# 34-SERDES_AND_DISPLAY_INTERFACE.net
KiCad netlist of a schematic drawn in Altium Designer
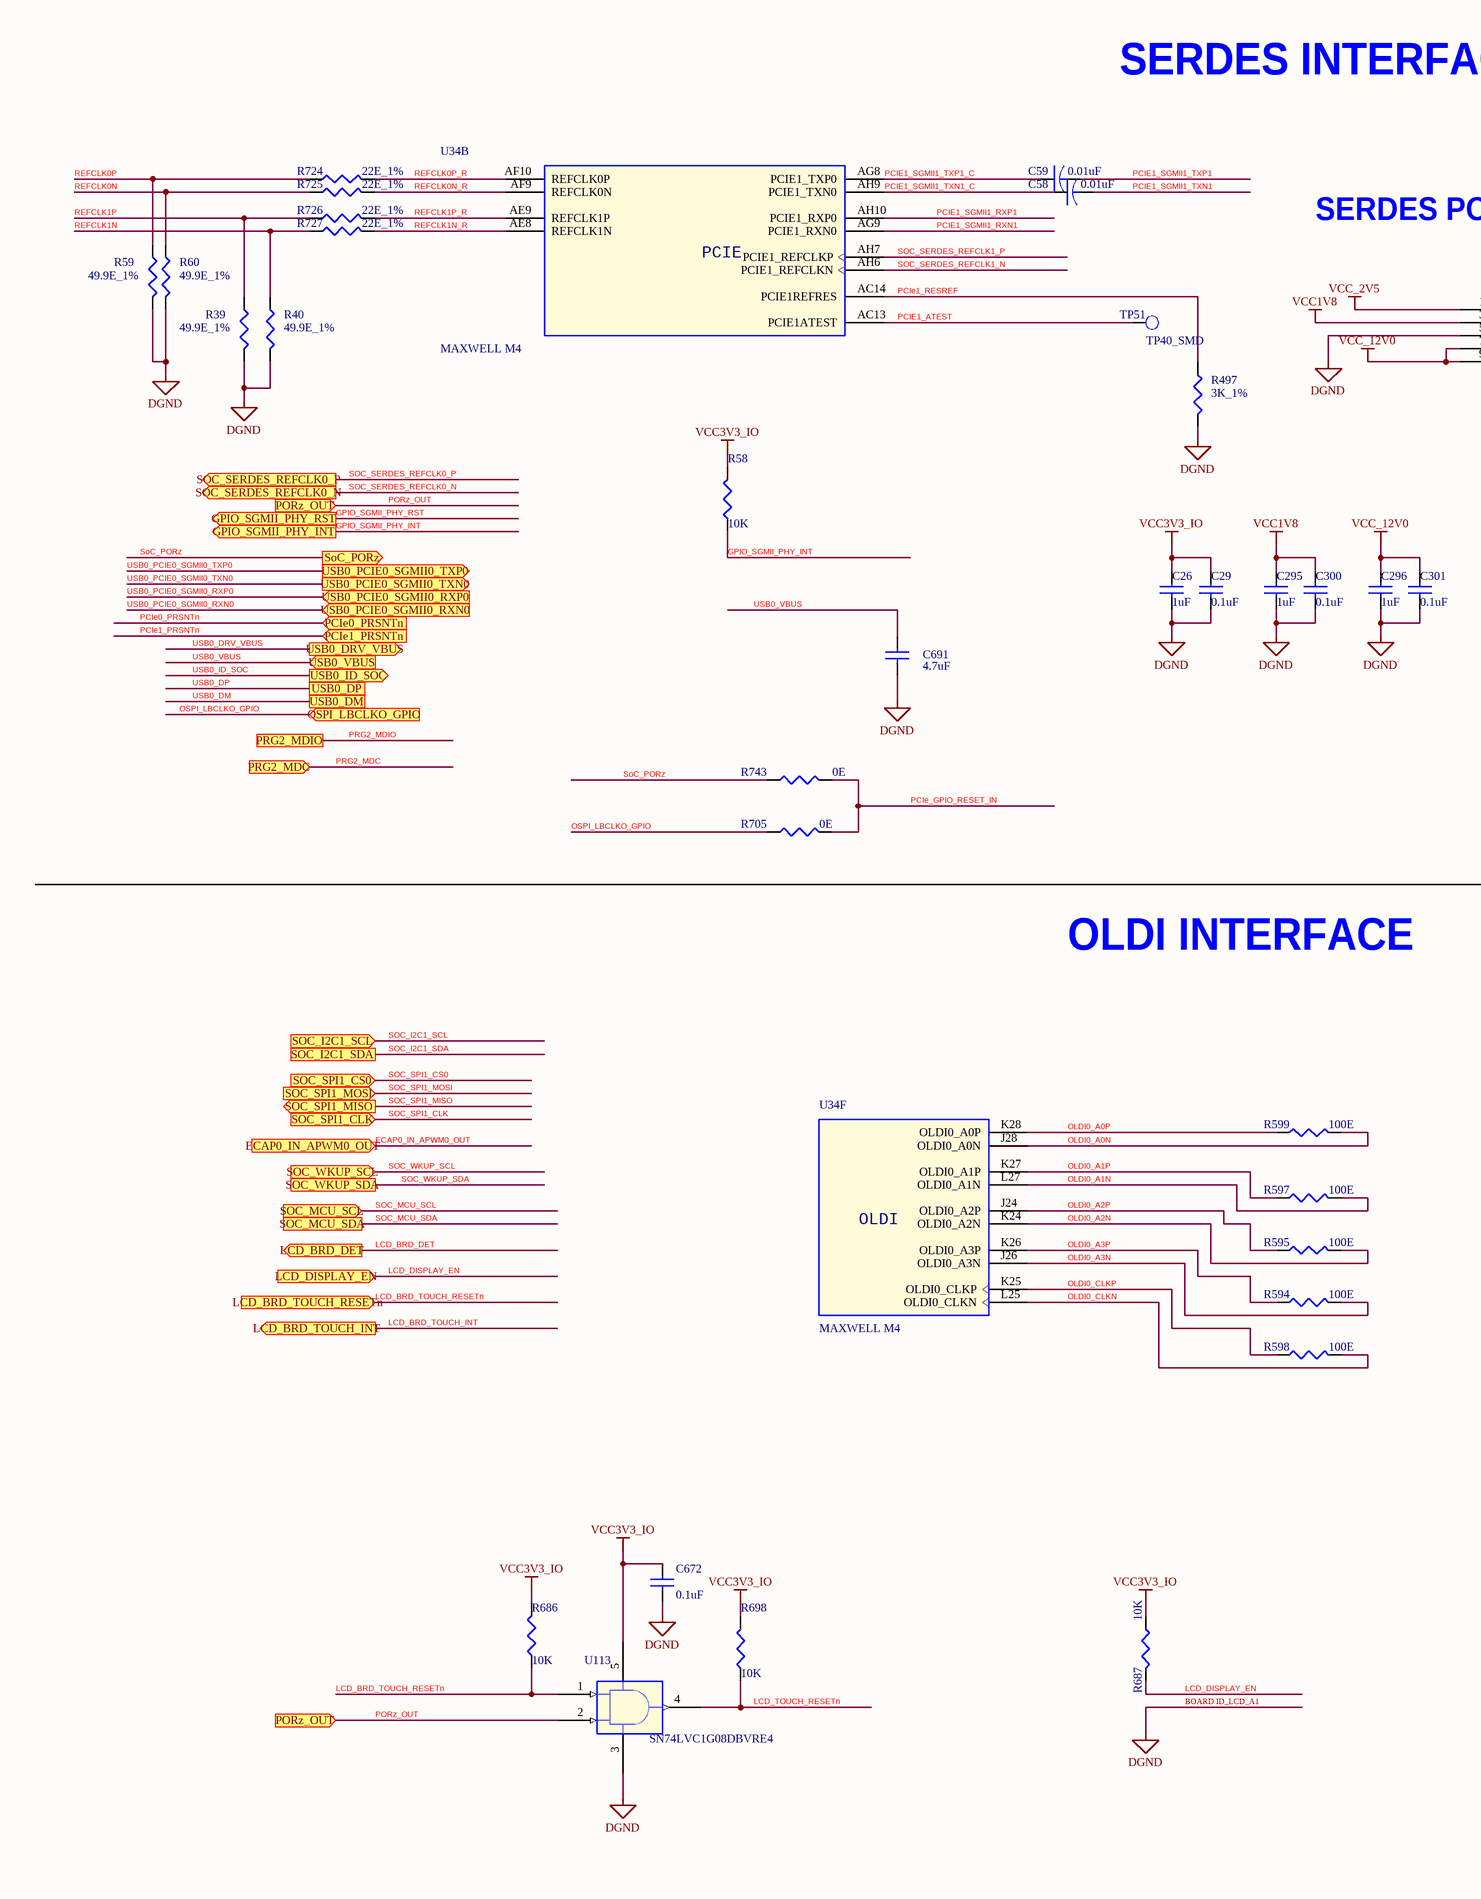
[diagram p0: 34-SERDES AND DISPLAY INTERFACE.SchDoc, left]
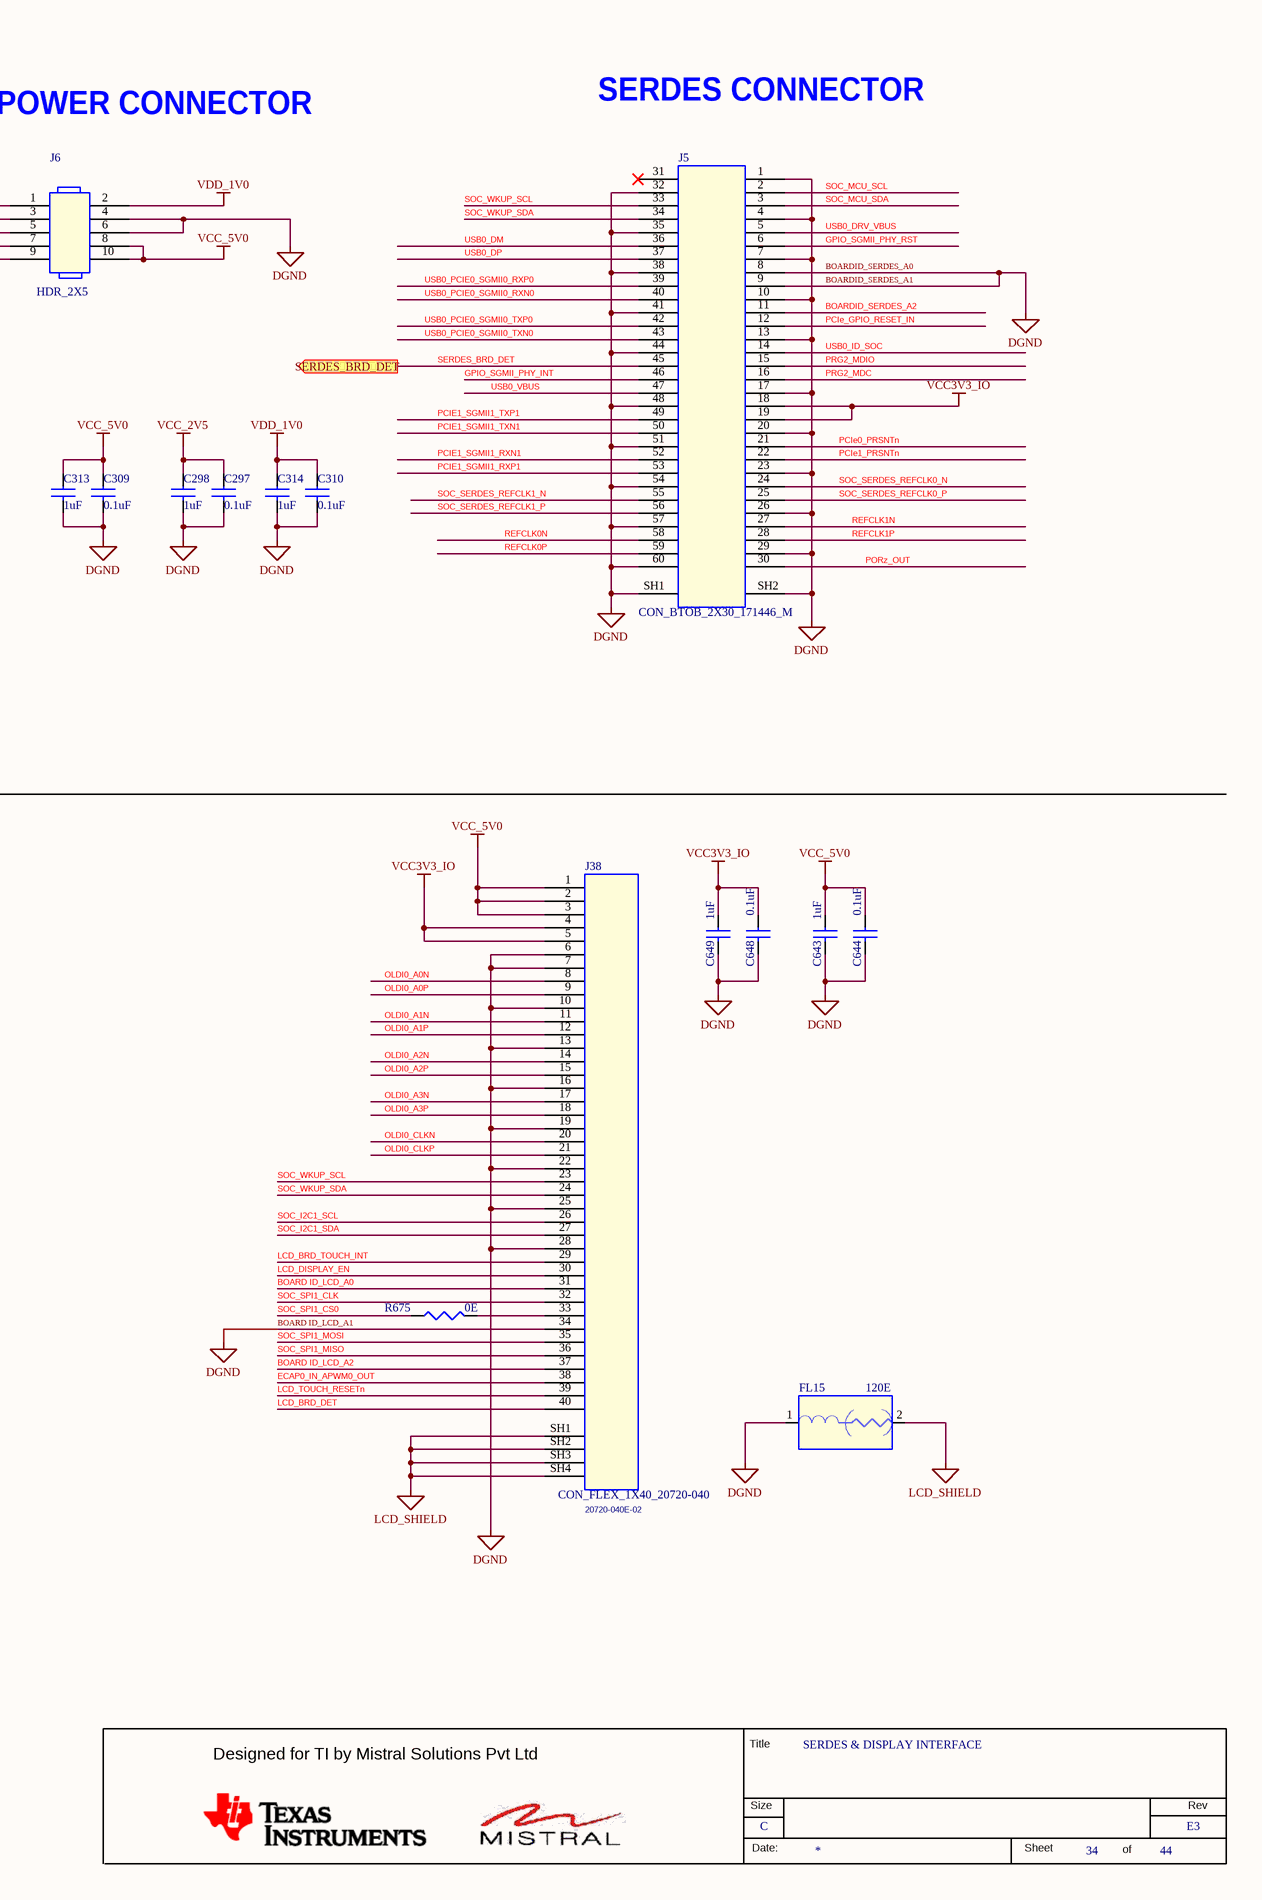
[diagram p1: 34-SERDES AND DISPLAY INTERFACE.SchDoc, right]

(export (version "E")
  (design (tool "Eeschema 10.0.6"))
  (components
    (comp (ref "C26")
      (value "1uF")
      (footprint "CAP0402_0-75")
      (description "CAP CERAMIC 1uF 16V 20% X5R 0402")
      (fields
        (field (name "MISTRAL PART NO") "120018020006-R")
        (field (name "MFR_PART_NUMBER") "EMK105BJ105MV-F")
      )
      (libsource (lib "*") (part "CAP_Dup5"))
    )
    (comp (ref "C29")
      (value "0.1uF")
      (footprint "CAP0201_0-5")
      (description "CAP CERAMIC 0.1uF 16V 10% X5R 0201")
      (fields (field (name "DISTRIBUTOR_PART_NUMBER") "490-16742-1-ND") (field (name "VOLTAGE") "16V"))
      (libsource (lib "*") (part "CAP_Dup5"))
    )
    (comp (ref "C58")
      (value "0.01uF")
      (footprint "CAP0402_0-75")
      (description "CAP CERAMIC 0.01uF 10V 10% X7R 0402")
      (fields (field (name "DISTRIBUTOR_PART_NUMBER") "478-7890-1-ND") (field (name "VOLTAGE") "10V"))
      (libsource (lib "*") (part "CAP"))
    )
    (comp (ref "C59")
      (value "0.01uF")
      (footprint "CAP0402_0-75")
      (description "CAP CERAMIC 0.01uF 10V 10% X7R 0402")
      (fields
        (field (name "MISTRAL PART NO") "120009030017-R")
        (field (name "MFR_PART_NUMBER") "0402ZC103KAT2A")
      )
      (libsource (lib "*") (part "CAP"))
    )
    (comp (ref "C295")
      (value "1uF")
      (footprint "CAP0402_0-75")
      (description "CAP CERAMIC 1uF 16V 20% X5R 0402")
      (fields
        (field (name "MISTRAL PART NO") "120018020006-R")
        (field (name "MFR_PART_NUMBER") "EMK105BJ105MV-F")
      )
      (libsource (lib "*") (part "CAP_Dup5"))
    )
    (comp (ref "C296")
      (value "1uF")
      (footprint "CAP0402_0-75")
      (description "CAP CERAMIC 1uF 16V 20% X5R 0402")
      (fields (field (name "DISTRIBUTOR_PART_NUMBER") "587-5514-1-ND") (field (name "VOLTAGE") "16V"))
      (libsource (lib "*") (part "CAP_Dup5"))
    )
    (comp (ref "C297")
      (value "0.1uF")
      (footprint "CAP0201_0-5")
      (description "CAP CERAMIC 0.1uF 16V 10% X5R 0201")
      (fields
        (field (name "MISTRAL PART NO") "120009030072-R")
        (field (name "MFR_PART_NUMBER") "GRM033R61C104KE84J")
      )
      (libsource (lib "*") (part "CAP_Dup5"))
    )
    (comp (ref "C298")
      (value "1uF")
      (footprint "CAP0402_0-75")
      (description "CAP CERAMIC 1uF 16V 20% X5R 0402")
      (fields (field (name "DISTRIBUTOR_PART_NUMBER") "587-5514-1-ND") (field (name "VOLTAGE") "16V"))
      (libsource (lib "*") (part "CAP_Dup5"))
    )
    (comp (ref "C300")
      (value "0.1uF")
      (footprint "CAP0201_0-5")
      (description "CAP CERAMIC 0.1uF 16V 10% X5R 0201")
      (fields (field (name "DISTRIBUTOR_PART_NUMBER") "490-16742-1-ND") (field (name "VOLTAGE") "16V"))
      (libsource (lib "*") (part "CAP_Dup5"))
    )
    (comp (ref "C301")
      (value "0.1uF")
      (footprint "CAP0201_0-5")
      (description "CAP CERAMIC 0.1uF 16V 10% X5R 0201")
      (fields
        (field (name "MISTRAL PART NO") "120009030072-R")
        (field (name "MFR_PART_NUMBER") "GRM033R61C104KE84J")
      )
      (libsource (lib "*") (part "CAP_Dup5"))
    )
    (comp (ref "C309")
      (value "0.1uF")
      (footprint "CAP0201_0-5")
      (description "CAP CERAMIC 0.1uF 16V 10% X5R 0201")
      (fields
        (field (name "MISTRAL PART NO") "120009030072-R")
        (field (name "MFR_PART_NUMBER") "GRM033R61C104KE84J")
      )
      (libsource (lib "*") (part "CAP_Dup5"))
    )
    (comp (ref "C310")
      (value "0.1uF")
      (footprint "CAP0201_0-5")
      (description "CAP CERAMIC 0.1uF 16V 10% X5R 0201")
      (fields
        (field (name "MISTRAL PART NO") "120009030072-R")
        (field (name "MFR_PART_NUMBER") "GRM033R61C104KE84J")
      )
      (libsource (lib "*") (part "CAP_Dup5"))
    )
    (comp (ref "C313")
      (value "1uF")
      (footprint "CAP0402_0-75")
      (description "CAP CERAMIC 1uF 16V 20% X5R 0402")
      (fields (field (name "DISTRIBUTOR_PART_NUMBER") "587-5514-1-ND") (field (name "VOLTAGE") "16V"))
      (libsource (lib "*") (part "CAP_Dup5"))
    )
    (comp (ref "C314")
      (value "1uF")
      (footprint "CAP0402_0-75")
      (description "CAP CERAMIC 1uF 16V 20% X5R 0402")
      (fields (field (name "DISTRIBUTOR_PART_NUMBER") "587-5514-1-ND") (field (name "VOLTAGE") "16V"))
      (libsource (lib "*") (part "CAP_Dup5"))
    )
    (comp (ref "C643")
      (value "1uF")
      (footprint "CAP0402_0-75")
      (description "CAP CERAMIC 1uF 16V 20% X5R 0402")
      (fields (field (name "DISTRIBUTOR_PART_NUMBER") "587-5514-1-ND") (field (name "VOLTAGE") "16V"))
      (libsource (lib "*") (part "CAP_Dup5"))
    )
    (comp (ref "C644")
      (value "0.1uF")
      (footprint "CAP0201_0-5")
      (description "CAP CERAMIC 0.1uF 16V 10% X5R 0201")
      (fields
        (field (name "MISTRAL PART NO") "120009030072-R")
        (field (name "MFR_PART_NUMBER") "GRM033R61C104KE84J")
      )
      (libsource (lib "*") (part "CAP_Dup5"))
    )
    (comp (ref "C648")
      (value "0.1uF")
      (footprint "CAP0201_0-5")
      (description "CAP CERAMIC 0.1uF 16V 10% X5R 0201")
      (fields
        (field (name "MISTRAL PART NO") "120009030072-R")
        (field (name "MFR_PART_NUMBER") "GRM033R61C104KE84J")
      )
      (libsource (lib "*") (part "CAP_Dup5"))
    )
    (comp (ref "C649")
      (value "1uF")
      (footprint "CAP0402_0-75")
      (description "CAP CERAMIC 1uF 16V 20% X5R 0402")
      (fields
        (field (name "MISTRAL PART NO") "120018020006-R")
        (field (name "MFR_PART_NUMBER") "EMK105BJ105MV-F")
      )
      (libsource (lib "*") (part "CAP_Dup5"))
    )
    (comp (ref "C672")
      (value "0.1uF")
      (footprint "CAP0201_0-5")
      (description "CAP CERAMIC 0.1uF 16V 10% X5R 0201")
      (fields
        (field (name "MISTRAL PART NO") "120009030072-R")
        (field (name "MFR_PART_NUMBER") "GRM033R61C104KE84J")
      )
      (libsource (lib "*") (part "CAP_Dup5"))
    )
    (comp (ref "C691")
      (value "4.7uF")
      (footprint "CAP0402_0-75")
      (description "CAP CERAMIC 4.7uF 10V 20% X5R 0402")
      (fields (field (name "DISTRIBUTOR_PART_NUMBER") "478-10791-1-ND") (field (name "VOLTAGE") "10V"))
      (libsource (lib "*") (part "CAP_Dup5"))
    )
    (comp (ref "FL15")
      (value "120E")
      (footprint "EMIFIL_BLM15A_0402_0-6")
      (description "FERRITE CHIP 120E 1.3A 0402")
      (fields (field (name "DISTRIBUTOR_PART_NUMBER") "490-5203-1-ND") (field (name "VOLTAGE") "NA"))
      (libsource (lib "*") (part "EMIFILTER_IND"))
    )
    (comp (ref "J5")
      (value "CON_BTOB_2X30_171446_M")
      (footprint "CON_BTOB2X30_171446_P_S_S_5-5")
      (description "CON BTOB 2X30 0.80MM PITCH MALE ST SMD")
      (fields (field (name "DISTRIBUTOR_PART_NUMBER") "1714461114-ND") (field (name "VOLTAGE") "NA"))
      (libsource (lib "*") (part "CON_BTOB_30X2_171446"))
    )
    (comp (ref "J6")
      (value "HDR_2X5")
      (footprint "HDR_2X5_TFC-105-01-D-A_S_T_5-6")
      (description "CON HDR 2X5 1.27MM PITCH ST TH")
      (fields
        (field (name "DISTRIBUTOR_PART_NUMBER") "NA")
        (field (name "MFR_PART_NUMBER") "TFC-105-01-L-D-A")
      )
      (libsource (lib "*") (part "HEADER_5X2"))
    )
    (comp (ref "J38")
      (value "CON_FLEX_1X40_20720-040")
      (footprint "CON_FLEX1X40_20720-040_S_R_S_2")
      (description "CON FPC 1X40 0.50MM PITCH RT SMD")
      (fields
        (field (name "MISTRAL PART NO") "150017100021-R")
        (field (name "MFR_PART_NUMBER") "20720-040E-02")
        (field (name "TOLERANCE") "NA")
      )
      (libsource (lib "*") (part "CON_FLEX_40X1_SH4"))
    )
    (comp (ref "R39")
      (value "49.9E_1%")
      (footprint "RES0201")
      (description "RES 49.9E 1/20W 1% 0201")
      (fields (field (name "DISTRIBUTOR_PART_NUMBER") "P49.9ABCT-ND") (field (name "TOLERANCE") "1%"))
      (libsource (lib "*") (part "RESISTOR_Dup5"))
    )
    (comp (ref "R40")
      (value "49.9E_1%")
      (footprint "RES0201")
      (description "RES 49.9E 1/20W 1% 0201")
      (fields (field (name "DISTRIBUTOR_PART_NUMBER") "P49.9ABCT-ND") (field (name "TOLERANCE") "1%"))
      (libsource (lib "*") (part "RESISTOR_Dup5"))
    )
    (comp (ref "R58")
      (value "10K")
      (footprint "RES0402_0-5")
      (description "RES 10K 1/16W 5% 0402")
      (fields (field (name "DISTRIBUTOR_PART_NUMBER") "311-10KJRCT-ND") (field (name "VOLTAGE") "NA"))
      (libsource (lib "*") (part "RESISTOR_Dup5"))
    )
    (comp (ref "R59")
      (value "49.9E_1%")
      (footprint "RES0201")
      (description "RES 49.9E 1/20W 1% 0201")
      (fields (field (name "DISTRIBUTOR_PART_NUMBER") "P49.9ABCT-ND") (field (name "TOLERANCE") "1%"))
      (libsource (lib "*") (part "RESISTOR_Dup5"))
    )
    (comp (ref "R60")
      (value "49.9E_1%")
      (footprint "RES0201")
      (description "RES 49.9E 1/20W 1% 0201")
      (fields (field (name "DISTRIBUTOR_PART_NUMBER") "P49.9ABCT-ND") (field (name "TOLERANCE") "1%"))
      (libsource (lib "*") (part "RESISTOR_Dup5"))
    )
    (comp (ref "R497")
      (value "3K_1%")
      (footprint "RES0402_0-5")
      (description "RES 3K 1/16W 1% 0402")
      (fields (field (name "DISTRIBUTOR_PART_NUMBER") "311-3KLRCT-ND") (field (name "VOLTAGE") "NA"))
      (libsource (lib "*") (part "RESISTOR_Dup5"))
    )
    (comp (ref "R594")
      (value "100E")
      (footprint "RES0201")
      (description "RES 100E 1/20W 5% 0201")
      (fields (field (name "DISTRIBUTOR_PART_NUMBER") "NA") (field (name "VOLTAGE") "50V"))
      (libsource (lib "*") (part "RESISTOR"))
    )
    (comp (ref "R595")
      (value "100E")
      (footprint "RES0201")
      (description "RES 100E 1/20W 5% 0201")
      (fields
        (field (name "MISTRAL PART NO") "110010070060-R")
        (field (name "MFR_PART_NUMBER") "NRC02J101TRF")
      )
      (libsource (lib "*") (part "RESISTOR"))
    )
    (comp (ref "R597")
      (value "100E")
      (footprint "RES0201")
      (description "RES 100E 1/20W 5% 0201")
      (fields (field (name "DISTRIBUTOR_PART_NUMBER") "NA") (field (name "VOLTAGE") "50V"))
      (libsource (lib "*") (part "RESISTOR"))
    )
    (comp (ref "R598")
      (value "100E")
      (footprint "RES0201")
      (description "RES 100E 1/20W 5% 0201")
      (fields
        (field (name "MISTRAL PART NO") "110010070060-R")
        (field (name "MFR_PART_NUMBER") "NRC02J101TRF")
      )
      (libsource (lib "*") (part "RESISTOR"))
    )
    (comp (ref "R599")
      (value "100E")
      (footprint "RES0201")
      (description "RES 100E 1/20W 5% 0201")
      (fields (field (name "DISTRIBUTOR_PART_NUMBER") "NA") (field (name "VOLTAGE") "50V"))
      (libsource (lib "*") (part "RESISTOR"))
    )
    (comp (ref "R675")
      (value "0E")
      (footprint "RES0402_0-5")
      (description "RES 0E 1/16W 0402")
      (fields
        (field (name "MISTRAL PART NO") "110010080019-P")
        (field (name "MFR_PART_NUMBER") "CRCW04020000Z0ED")
      )
      (libsource (lib "*") (part "RESISTOR_Dup5"))
    )
    (comp (ref "R686")
      (value "10K")
      (footprint "RES0402_0-5")
      (description "RES 10K 1/16W 5% 0402")
      (fields (field (name "DISTRIBUTOR_PART_NUMBER") "311-10KJRCT-ND") (field (name "VOLTAGE") "NA"))
      (libsource (lib "*") (part "RESISTOR_Dup5"))
    )
    (comp (ref "R687")
      (value "10K")
      (footprint "RES0402_0-5")
      (description "RES 10K 1/16W 5% 0402")
      (fields (field (name "DISTRIBUTOR_PART_NUMBER") "311-10KJRCT-ND") (field (name "VOLTAGE") "NA"))
      (libsource (lib "*") (part "RESISTOR_Dup5"))
    )
    (comp (ref "R698")
      (value "10K")
      (footprint "RES0402_0-5")
      (description "RES 10K 1/16W 5% 0402")
      (fields (field (name "DISTRIBUTOR_PART_NUMBER") "311-10KJRCT-ND") (field (name "VOLTAGE") "NA"))
      (libsource (lib "*") (part "RESISTOR_Dup5"))
    )
    (comp (ref "R705")
      (value "0E")
      (footprint "RES0402_0-5")
      (description "RES 0E 1/16W 0402")
      (fields
        (field (name "MISTRAL PART NO") "110010080019-P")
        (field (name "MFR_PART_NUMBER") "CRCW04020000Z0ED")
      )
      (libsource (lib "*") (part "RESISTOR_Dup4"))
    )
    (comp (ref "R724")
      (value "22E_1%")
      (footprint "RES0402")
      (description "RES 22E 1/16W 1% 0402")
      (fields
        (field (name "MISTRAL PART NO") "110009090004-P")
        (field (name "MFR_PART_NUMBER") "RC0402FR-0722RL")
      )
      (libsource (lib "*") (part "RESISTOR_Dup5"))
    )
    (comp (ref "R725")
      (value "22E_1%")
      (footprint "RES0402")
      (description "RES 22E 1/16W 1% 0402")
      (fields
        (field (name "CUST_PART_NUMBER") "4700-80047E")
        (field (name "DISTRIBUTOR_PART_NUMBER") "311-22.0LRCT-ND")
      )
      (libsource (lib "*") (part "RESISTOR_Dup5"))
    )
    (comp (ref "R726")
      (value "22E_1%")
      (footprint "RES0402")
      (description "RES 22E 1/16W 1% 0402")
      (fields
        (field (name "CUST_PART_NUMBER") "4700-80047E")
        (field (name "DISTRIBUTOR_PART_NUMBER") "311-22.0LRCT-ND")
      )
      (libsource (lib "*") (part "RESISTOR_Dup5"))
    )
    (comp (ref "R727")
      (value "22E_1%")
      (footprint "RES0402")
      (description "RES 22E 1/16W 1% 0402")
      (fields
        (field (name "MISTRAL PART NO") "110009090004-P")
        (field (name "MFR_PART_NUMBER") "RC0402FR-0722RL")
      )
      (libsource (lib "*") (part "RESISTOR_Dup5"))
    )
    (comp (ref "R743")
      (value "0E")
      (footprint "RES0402_0-5")
      (description "RES 0E 1/16W 0402")
      (fields
        (field (name "MISTRAL PART NO") "110010080019-P")
        (field (name "MFR_PART_NUMBER") "CRCW04020000Z0ED")
      )
      (libsource (lib "*") (part "RESISTOR_Dup4"))
    )
    (comp (ref "TP51")
      (value "TP40_SMD")
      (footprint "TP40_SMD")
      (description "TESTPOINT CIR 40 SMD")
      (fields (field (name "DISTRIBUTOR_PART_NUMBER") "NA") (field (name "MISTRAL PART NO") "130009030933"))
      (libsource (lib "*") (part "TESTPOINT"))
    )
    (comp (ref "U34")
      (value "MAXWELL M4")
      (footprint "BGA784_31-49_910X910_1-7")
      (description "IC MAXWELL MICRO CONTROLLER UNIT BGA784")
      (fields
        (field (name "MISTRAL PART NO") "141217100003")
        (field (name "MFR_PART_NUMBER") "MAXWELL M4_EVM")
        (field (name "DISTRIBUTOR_PART_NUMBER") "NA")
      )
      (libsource (lib "") (part "AM654X_BGA784_1"))
    )
    (comp (ref "U113")
      (value "SN74LVC1G08DBVRE4")
      (footprint "SOT23-5")
      (description "IC SINGLE 2-INPUT POSITIVE AND GATE SOT23-5")
      (fields
        (field (name "MISTRAL PART NO") "141009060026-R")
        (field (name "DISTRIBUTOR_PART_NUMBER") "SN74LVC1G08DBVRE4-ND")
      )
      (libsource (lib "*") (part "SN74LVC1G08DBVRE4_SOT23-5"))
    )
  )
  (nets
    (net (code "1") (name "/BOARD ID_LCD_A0") (class "Default")
      (node (ref "J38") (pin "31") (pinfunction "31_31") (pintype "passive"))
    )
    (net (code "2") (name "/BOARD ID_LCD_A2") (class "Default")
      (node (ref "J38") (pin "37") (pinfunction "37_37") (pintype "passive"))
    )
    (net (code "3") (name "/BOARDID_SERDES_A2") (class "Default")
      (node (ref "J5") (pin "11") (pinfunction "11_11") (pintype "passive"))
    )
    (net (code "4") (name "/ECAP0_IN_APWM0_OUT") (class "Default")
      (node (ref "J38") (pin "38") (pinfunction "38_38") (pintype "passive"))
    )
    (net (code "5") (name "/GPIO_SGMII_PHY_INT") (class "Default")
      (node (ref "J5") (pin "46") (pinfunction "46_46") (pintype "passive"))
      (node (ref "R58") (pin "1") (pinfunction "1_1") (pintype "passive"))
    )
    (net (code "6") (name "/GPIO_SGMII_PHY_RST") (class "Default")
      (node (ref "J5") (pin "6") (pinfunction "6_6") (pintype "passive"))
    )
    (net (code "7") (name "/LCD_BRD_DET") (class "Default")
      (node (ref "J38") (pin "40") (pinfunction "40_40") (pintype "passive"))
    )
    (net (code "8") (name "/LCD_BRD_TOUCH_INT") (class "Default")
      (node (ref "J38") (pin "29") (pinfunction "29_29") (pintype "passive"))
    )
    (net (code "9") (name "/LCD_BRD_TOUCH_RESETn") (class "Default")
      (node (ref "R686") (pin "1") (pinfunction "1_1") (pintype "passive"))
      (node (ref "U113") (pin "1") (pinfunction "A_1") (pintype "input"))
    )
    (net (code "10") (name "/LCD_DISPLAY_EN") (class "Default")
      (node (ref "J38") (pin "30") (pinfunction "30_30") (pintype "passive"))
      (node (ref "R687") (pin "2") (pinfunction "2_2") (pintype "passive"))
    )
    (net (code "11") (name "/LCD_TOUCH_RESETn") (class "Default")
      (node (ref "J38") (pin "39") (pinfunction "39_39") (pintype "passive"))
      (node (ref "R698") (pin "1") (pinfunction "1_1") (pintype "passive"))
      (node (ref "U113") (pin "4") (pinfunction "Y_4") (pintype "output"))
    )
    (net (code "12") (name "/OLDI0_A0N") (class "Default")
      (node (ref "J38") (pin "8") (pinfunction "8_8") (pintype "passive"))
      (node (ref "R599") (pin "2") (pinfunction "2_2") (pintype "passive"))
      (node (ref "U34") (pin "J28") (pinfunction "OLDI0_A0N_J28") (pintype "passive"))
    )
    (net (code "13") (name "/OLDI0_A0P") (class "Default")
      (node (ref "J38") (pin "9") (pinfunction "9_9") (pintype "passive"))
      (node (ref "R599") (pin "1") (pinfunction "1_1") (pintype "passive"))
      (node (ref "U34") (pin "K28") (pinfunction "OLDI0_A0P_K28") (pintype "passive"))
    )
    (net (code "14") (name "/OLDI0_A1N") (class "Default")
      (node (ref "J38") (pin "11") (pinfunction "11_11") (pintype "passive"))
      (node (ref "R597") (pin "2") (pinfunction "2_2") (pintype "passive"))
      (node (ref "U34") (pin "L27") (pinfunction "OLDI0_A1N_L27") (pintype "passive"))
    )
    (net (code "15") (name "/OLDI0_A1P") (class "Default")
      (node (ref "J38") (pin "12") (pinfunction "12_12") (pintype "passive"))
      (node (ref "R597") (pin "1") (pinfunction "1_1") (pintype "passive"))
      (node (ref "U34") (pin "K27") (pinfunction "OLDI0_A1P_K27") (pintype "passive"))
    )
    (net (code "16") (name "/OLDI0_A2N") (class "Default")
      (node (ref "J38") (pin "14") (pinfunction "14_14") (pintype "passive"))
      (node (ref "R595") (pin "2") (pinfunction "2_2") (pintype "passive"))
      (node (ref "U34") (pin "K24") (pinfunction "OLDI0_A2N_K24") (pintype "passive"))
    )
    (net (code "17") (name "/OLDI0_A2P") (class "Default")
      (node (ref "J38") (pin "15") (pinfunction "15_15") (pintype "passive"))
      (node (ref "R595") (pin "1") (pinfunction "1_1") (pintype "passive"))
      (node (ref "U34") (pin "J24") (pinfunction "OLDI0_A2P_J24") (pintype "passive"))
    )
    (net (code "18") (name "/OLDI0_A3N") (class "Default")
      (node (ref "J38") (pin "17") (pinfunction "17_17") (pintype "passive"))
      (node (ref "R594") (pin "2") (pinfunction "2_2") (pintype "passive"))
      (node (ref "U34") (pin "J26") (pinfunction "OLDI0_A3N_J26") (pintype "passive"))
    )
    (net (code "19") (name "/OLDI0_A3P") (class "Default")
      (node (ref "J38") (pin "18") (pinfunction "18_18") (pintype "passive"))
      (node (ref "R594") (pin "1") (pinfunction "1_1") (pintype "passive"))
      (node (ref "U34") (pin "K26") (pinfunction "OLDI0_A3P_K26") (pintype "passive"))
    )
    (net (code "20") (name "/OLDI0_CLKN") (class "Default")
      (node (ref "J38") (pin "20") (pinfunction "20_20") (pintype "passive"))
      (node (ref "R598") (pin "2") (pinfunction "2_2") (pintype "passive"))
      (node (ref "U34") (pin "L25") (pinfunction "OLDI0_CLKN_L25") (pintype "passive"))
    )
    (net (code "21") (name "/OLDI0_CLKP") (class "Default")
      (node (ref "J38") (pin "21") (pinfunction "21_21") (pintype "passive"))
      (node (ref "R598") (pin "1") (pinfunction "1_1") (pintype "passive"))
      (node (ref "U34") (pin "K25") (pinfunction "OLDI0_CLKP_K25") (pintype "passive"))
    )
    (net (code "22") (name "/OSPI_LBCLKO_GPIO") (class "Default")
      (node (ref "R705") (pin "2") (pinfunction "2_2") (pintype "passive"))
    )
    (net (code "23") (name "/PCIE1_ATEST") (class "Default")
      (node (ref "TP51") (pin "1") (pinfunction "TP_1") (pintype "passive"))
      (node (ref "U34") (pin "AC13") (pinfunction "PCIE1ATEST_AC13") (pintype "passive"))
    )
    (net (code "24") (name "/PCIE1_SGMII1_RXN1") (class "Default")
      (node (ref "J5") (pin "52") (pinfunction "52_52") (pintype "passive"))
      (node (ref "U34") (pin "AG9") (pinfunction "PCIE1_RXN0_AG9") (pintype "passive"))
    )
    (net (code "25") (name "/PCIE1_SGMII1_RXP1") (class "Default")
      (node (ref "J5") (pin "53") (pinfunction "53_53") (pintype "passive"))
      (node (ref "U34") (pin "AH10") (pinfunction "PCIE1_RXP0_AH10") (pintype "passive"))
    )
    (net (code "26") (name "/PCIE1_SGMII1_TXN1") (class "Default")
      (node (ref "C58") (pin "2") (pinfunction "2_2") (pintype "passive"))
      (node (ref "J5") (pin "50") (pinfunction "50_50") (pintype "passive"))
    )
    (net (code "27") (name "/PCIE1_SGMII1_TXN1_C") (class "Default")
      (node (ref "C58") (pin "1") (pinfunction "1_1") (pintype "passive"))
      (node (ref "U34") (pin "AH9") (pinfunction "PCIE1_TXN0_AH9") (pintype "passive"))
    )
    (net (code "28") (name "/PCIE1_SGMII1_TXP1") (class "Default")
      (node (ref "C59") (pin "2") (pinfunction "2_2") (pintype "passive"))
      (node (ref "J5") (pin "49") (pinfunction "49_49") (pintype "passive"))
    )
    (net (code "29") (name "/PCIE1_SGMII1_TXP1_C") (class "Default")
      (node (ref "C59") (pin "1") (pinfunction "1_1") (pintype "passive"))
      (node (ref "U34") (pin "AG8") (pinfunction "PCIE1_TXP0_AG8") (pintype "passive"))
    )
    (net (code "30") (name "/PCIe0_PRSNTn") (class "Default")
      (node (ref "J5") (pin "21") (pinfunction "21_21") (pintype "passive"))
    )
    (net (code "31") (name "/PCIe1_PRSNTn") (class "Default")
      (node (ref "J5") (pin "22") (pinfunction "22_22") (pintype "passive"))
    )
    (net (code "32") (name "/PCIe1_RESREF") (class "Default")
      (node (ref "R497") (pin "1") (pinfunction "1_1") (pintype "passive"))
      (node (ref "U34") (pin "AC14") (pinfunction "PCIE1REFRES_AC14") (pintype "passive"))
    )
    (net (code "33") (name "/PCIe_GPIO_RESET_IN") (class "Default")
      (node (ref "J5") (pin "12") (pinfunction "12_12") (pintype "passive"))
      (node (ref "R705") (pin "1") (pinfunction "1_1") (pintype "passive"))
      (node (ref "R743") (pin "1") (pinfunction "1_1") (pintype "passive"))
    )
    (net (code "34") (name "/PORz_OUT") (class "Default")
      (node (ref "J5") (pin "30") (pinfunction "30_30") (pintype "passive"))
      (node (ref "U113") (pin "2") (pinfunction "B_2") (pintype "input"))
    )
    (net (code "35") (name "/PRG2_MDC") (class "Default")
      (node (ref "J5") (pin "16") (pinfunction "16_16") (pintype "passive"))
    )
    (net (code "36") (name "/PRG2_MDIO") (class "Default")
      (node (ref "J5") (pin "15") (pinfunction "15_15") (pintype "passive"))
    )
    (net (code "37") (name "/REFCLK0N") (class "Default")
      (node (ref "J5") (pin "58") (pinfunction "58_58") (pintype "passive"))
      (node (ref "R60") (pin "1") (pinfunction "1_1") (pintype "passive"))
      (node (ref "R725") (pin "1") (pinfunction "1_1") (pintype "passive"))
    )
    (net (code "38") (name "/REFCLK0N_R") (class "Default")
      (node (ref "R725") (pin "2") (pinfunction "2_2") (pintype "passive"))
      (node (ref "U34") (pin "AF9") (pinfunction "REFCLK0N_AF9") (pintype "passive"))
    )
    (net (code "39") (name "/REFCLK0P") (class "Default")
      (node (ref "J5") (pin "59") (pinfunction "59_59") (pintype "passive"))
      (node (ref "R59") (pin "1") (pinfunction "1_1") (pintype "passive"))
      (node (ref "R724") (pin "1") (pinfunction "1_1") (pintype "passive"))
    )
    (net (code "40") (name "/REFCLK0P_R") (class "Default")
      (node (ref "R724") (pin "2") (pinfunction "2_2") (pintype "passive"))
      (node (ref "U34") (pin "AF10") (pinfunction "REFCLK0P_AF10") (pintype "passive"))
    )
    (net (code "41") (name "/REFCLK1N") (class "Default")
      (node (ref "J5") (pin "27") (pinfunction "27_27") (pintype "passive"))
      (node (ref "R40") (pin "1") (pinfunction "1_1") (pintype "passive"))
      (node (ref "R727") (pin "1") (pinfunction "1_1") (pintype "passive"))
    )
    (net (code "42") (name "/REFCLK1N_R") (class "Default")
      (node (ref "R727") (pin "2") (pinfunction "2_2") (pintype "passive"))
      (node (ref "U34") (pin "AE8") (pinfunction "REFCLK1N_AE8") (pintype "passive"))
    )
    (net (code "43") (name "/REFCLK1P") (class "Default")
      (node (ref "J5") (pin "28") (pinfunction "28_28") (pintype "passive"))
      (node (ref "R39") (pin "1") (pinfunction "1_1") (pintype "passive"))
      (node (ref "R726") (pin "1") (pinfunction "1_1") (pintype "passive"))
    )
    (net (code "44") (name "/REFCLK1P_R") (class "Default")
      (node (ref "R726") (pin "2") (pinfunction "2_2") (pintype "passive"))
      (node (ref "U34") (pin "AE9") (pinfunction "REFCLK1P_AE9") (pintype "passive"))
    )
    (net (code "45") (name "/SERDES_BRD_DET") (class "Default")
      (node (ref "J5") (pin "45") (pinfunction "45_45") (pintype "passive"))
    )
    (net (code "46") (name "/SOC_I2C1_SCL") (class "Default")
      (node (ref "J38") (pin "26") (pinfunction "26_26") (pintype "passive"))
    )
    (net (code "47") (name "/SOC_I2C1_SDA") (class "Default")
      (node (ref "J38") (pin "27") (pinfunction "27_27") (pintype "passive"))
    )
    (net (code "48") (name "/SOC_MCU_SCL") (class "Default")
      (node (ref "J5") (pin "2") (pinfunction "2_2") (pintype "passive"))
    )
    (net (code "49") (name "/SOC_MCU_SDA") (class "Default")
      (node (ref "J5") (pin "3") (pinfunction "3_3") (pintype "passive"))
    )
    (net (code "50") (name "/SOC_SERDES_REFCLK0_N") (class "Default")
      (node (ref "J5") (pin "24") (pinfunction "24_24") (pintype "passive"))
    )
    (net (code "51") (name "/SOC_SERDES_REFCLK0_P") (class "Default")
      (node (ref "J5") (pin "25") (pinfunction "25_25") (pintype "passive"))
    )
    (net (code "52") (name "/SOC_SERDES_REFCLK1_N") (class "Default")
      (node (ref "J5") (pin "55") (pinfunction "55_55") (pintype "passive"))
      (node (ref "U34") (pin "AH6") (pinfunction "PCIE1_REFCLKN_AH6") (pintype "passive"))
    )
    (net (code "53") (name "/SOC_SERDES_REFCLK1_P") (class "Default")
      (node (ref "J5") (pin "56") (pinfunction "56_56") (pintype "passive"))
      (node (ref "U34") (pin "AH7") (pinfunction "PCIE1_REFCLKP_AH7") (pintype "passive"))
    )
    (net (code "54") (name "/SOC_SPI1_CLK") (class "Default")
      (node (ref "J38") (pin "32") (pinfunction "32_32") (pintype "passive"))
    )
    (net (code "55") (name "/SOC_SPI1_CS0") (class "Default")
      (node (ref "R675") (pin "1") (pinfunction "1_1") (pintype "passive"))
    )
    (net (code "56") (name "/SOC_SPI1_MISO") (class "Default")
      (node (ref "J38") (pin "36") (pinfunction "36_36") (pintype "passive"))
    )
    (net (code "57") (name "/SOC_SPI1_MOSI") (class "Default")
      (node (ref "J38") (pin "35") (pinfunction "35_35") (pintype "passive"))
    )
    (net (code "58") (name "/SOC_WKUP_SCL") (class "Default")
      (node (ref "J38") (pin "23") (pinfunction "23_23") (pintype "passive"))
      (node (ref "J5") (pin "33") (pinfunction "33_33") (pintype "passive"))
    )
    (net (code "59") (name "/SOC_WKUP_SDA") (class "Default")
      (node (ref "J38") (pin "24") (pinfunction "24_24") (pintype "passive"))
      (node (ref "J5") (pin "34") (pinfunction "34_34") (pintype "passive"))
    )
    (net (code "60") (name "/SoC_PORz") (class "Default")
      (node (ref "R743") (pin "2") (pinfunction "2_2") (pintype "passive"))
    )
    (net (code "61") (name "/USB0_DM") (class "Default")
      (node (ref "J5") (pin "36") (pinfunction "36_36") (pintype "passive"))
    )
    (net (code "62") (name "/USB0_DP") (class "Default")
      (node (ref "J5") (pin "37") (pinfunction "37_37") (pintype "passive"))
    )
    (net (code "63") (name "/USB0_DRV_VBUS") (class "Default")
      (node (ref "J5") (pin "5") (pinfunction "5_5") (pintype "passive"))
    )
    (net (code "64") (name "/USB0_ID_SOC") (class "Default")
      (node (ref "J5") (pin "14") (pinfunction "14_14") (pintype "passive"))
    )
    (net (code "65") (name "/USB0_PCIE0_SGMII0_RXN0") (class "Default")
      (node (ref "J5") (pin "40") (pinfunction "40_40") (pintype "passive"))
    )
    (net (code "66") (name "/USB0_PCIE0_SGMII0_RXP0") (class "Default")
      (node (ref "J5") (pin "39") (pinfunction "39_39") (pintype "passive"))
    )
    (net (code "67") (name "/USB0_PCIE0_SGMII0_TXN0") (class "Default")
      (node (ref "J5") (pin "43") (pinfunction "43_43") (pintype "passive"))
    )
    (net (code "68") (name "/USB0_PCIE0_SGMII0_TXP0") (class "Default")
      (node (ref "J5") (pin "42") (pinfunction "42_42") (pintype "passive"))
    )
    (net (code "69") (name "/USB0_VBUS") (class "Default")
      (node (ref "C691") (pin "1") (pinfunction "1_1") (pintype "passive"))
      (node (ref "J5") (pin "47") (pinfunction "47_47") (pintype "passive"))
    )
    (net (code "70") (name "DGND") (class "Default")
      (node (ref "C26") (pin "2") (pinfunction "2_2") (pintype "passive"))
      (node (ref "C29") (pin "2") (pinfunction "2_2") (pintype "passive"))
      (node (ref "C295") (pin "2") (pinfunction "2_2") (pintype "passive"))
      (node (ref "C296") (pin "2") (pinfunction "2_2") (pintype "passive"))
      (node (ref "C297") (pin "2") (pinfunction "2_2") (pintype "passive"))
      (node (ref "C298") (pin "2") (pinfunction "2_2") (pintype "passive"))
      (node (ref "C300") (pin "2") (pinfunction "2_2") (pintype "passive"))
      (node (ref "C301") (pin "2") (pinfunction "2_2") (pintype "passive"))
      (node (ref "C309") (pin "2") (pinfunction "2_2") (pintype "passive"))
      (node (ref "C310") (pin "2") (pinfunction "2_2") (pintype "passive"))
      (node (ref "C313") (pin "2") (pinfunction "2_2") (pintype "passive"))
      (node (ref "C314") (pin "2") (pinfunction "2_2") (pintype "passive"))
      (node (ref "C643") (pin "2") (pinfunction "2_2") (pintype "passive"))
      (node (ref "C644") (pin "2") (pinfunction "2_2") (pintype "passive"))
      (node (ref "C648") (pin "2") (pinfunction "2_2") (pintype "passive"))
      (node (ref "C649") (pin "2") (pinfunction "2_2") (pintype "passive"))
      (node (ref "C672") (pin "2") (pinfunction "2_2") (pintype "passive"))
      (node (ref "C691") (pin "2") (pinfunction "2_2") (pintype "passive"))
      (node (ref "FL15") (pin "1") (pinfunction "1_1") (pintype "passive"))
      (node (ref "J38") (pin "10") (pinfunction "10_10") (pintype "passive"))
      (node (ref "J38") (pin "13") (pinfunction "13_13") (pintype "passive"))
      (node (ref "J38") (pin "16") (pinfunction "16_16") (pintype "passive"))
      (node (ref "J38") (pin "19") (pinfunction "19_19") (pintype "passive"))
      (node (ref "J38") (pin "22") (pinfunction "22_22") (pintype "passive"))
      (node (ref "J38") (pin "25") (pinfunction "25_25") (pintype "passive"))
      (node (ref "J38") (pin "28") (pinfunction "28_28") (pintype "passive"))
      (node (ref "J38") (pin "34") (pinfunction "34_34") (pintype "passive"))
      (node (ref "J38") (pin "6") (pinfunction "6_6") (pintype "passive"))
      (node (ref "J38") (pin "7") (pinfunction "7_7") (pintype "passive"))
      (node (ref "J5") (pin "1") (pinfunction "1_1") (pintype "passive"))
      (node (ref "J5") (pin "10") (pinfunction "10_10") (pintype "passive"))
      (node (ref "J5") (pin "13") (pinfunction "13_13") (pintype "passive"))
      (node (ref "J5") (pin "17") (pinfunction "17_17") (pintype "passive"))
      (node (ref "J5") (pin "20") (pinfunction "20_20") (pintype "passive"))
      (node (ref "J5") (pin "23") (pinfunction "23_23") (pintype "passive"))
      (node (ref "J5") (pin "26") (pinfunction "26_26") (pintype "passive"))
      (node (ref "J5") (pin "29") (pinfunction "29_29") (pintype "passive"))
      (node (ref "J5") (pin "32") (pinfunction "32_32") (pintype "passive"))
      (node (ref "J5") (pin "35") (pinfunction "35_35") (pintype "passive"))
      (node (ref "J5") (pin "38") (pinfunction "38_38") (pintype "passive"))
      (node (ref "J5") (pin "4") (pinfunction "4_4") (pintype "passive"))
      (node (ref "J5") (pin "41") (pinfunction "41_41") (pintype "passive"))
      (node (ref "J5") (pin "44") (pinfunction "44_44") (pintype "passive"))
      (node (ref "J5") (pin "48") (pinfunction "48_48") (pintype "passive"))
      (node (ref "J5") (pin "51") (pinfunction "51_51") (pintype "passive"))
      (node (ref "J5") (pin "54") (pinfunction "54_54") (pintype "passive"))
      (node (ref "J5") (pin "57") (pinfunction "57_57") (pintype "passive"))
      (node (ref "J5") (pin "60") (pinfunction "60_60") (pintype "passive"))
      (node (ref "J5") (pin "7") (pinfunction "7_7") (pintype "passive"))
      (node (ref "J5") (pin "8") (pinfunction "8_8") (pintype "passive"))
      (node (ref "J5") (pin "9") (pinfunction "9_9") (pintype "passive"))
      (node (ref "J5") (pin "SH1") (pinfunction "SH1_SH1") (pintype "passive"))
      (node (ref "J5") (pin "SH2") (pinfunction "SH2_SH2") (pintype "passive"))
      (node (ref "J6") (pin "4") (pinfunction "4_4") (pintype "passive"))
      (node (ref "J6") (pin "5") (pinfunction "5_5") (pintype "passive"))
      (node (ref "J6") (pin "6") (pinfunction "6_6") (pintype "passive"))
      (node (ref "R39") (pin "2") (pinfunction "2_2") (pintype "passive"))
      (node (ref "R40") (pin "2") (pinfunction "2_2") (pintype "passive"))
      (node (ref "R497") (pin "2") (pinfunction "2_2") (pintype "passive"))
      (node (ref "R59") (pin "2") (pinfunction "2_2") (pintype "passive"))
      (node (ref "R60") (pin "2") (pinfunction "2_2") (pintype "passive"))
      (node (ref "U113") (pin "3") (pinfunction "GND_3") (pintype "power_in"))
    )
    (net (code "71") (name "LCD_SHIELD") (class "Default")
      (node (ref "FL15") (pin "2") (pinfunction "2_2") (pintype "passive"))
      (node (ref "J38") (pin "SH1") (pinfunction "SH1_SH1") (pintype "passive"))
      (node (ref "J38") (pin "SH2") (pinfunction "SH2_SH2") (pintype "passive"))
      (node (ref "J38") (pin "SH3") (pinfunction "SH3_SH3") (pintype "passive"))
      (node (ref "J38") (pin "SH4") (pinfunction "SH4_SH4") (pintype "passive"))
    )
    (net (code "72") (name "Net-(J38-Pad33)") (class "Default")
      (node (ref "J38") (pin "33") (pinfunction "33_33") (pintype "passive"))
      (node (ref "R675") (pin "2") (pinfunction "2_2") (pintype "passive"))
    )
    (net (code "73") (name "VCC1V8") (class "Default")
      (node (ref "C295") (pin "1") (pinfunction "1_1") (pintype "passive"))
      (node (ref "C300") (pin "1") (pinfunction "1_1") (pintype "passive"))
      (node (ref "J6") (pin "3") (pinfunction "3_3") (pintype "passive"))
    )
    (net (code "74") (name "VCC3V3_IO") (class "Default")
      (node (ref "C26") (pin "1") (pinfunction "1_1") (pintype "passive"))
      (node (ref "C29") (pin "1") (pinfunction "1_1") (pintype "passive"))
      (node (ref "C648") (pin "1") (pinfunction "1_1") (pintype "passive"))
      (node (ref "C649") (pin "1") (pinfunction "1_1") (pintype "passive"))
      (node (ref "C672") (pin "1") (pinfunction "1_1") (pintype "passive"))
      (node (ref "J38") (pin "4") (pinfunction "4_4") (pintype "passive"))
      (node (ref "J38") (pin "5") (pinfunction "5_5") (pintype "passive"))
      (node (ref "J5") (pin "18") (pinfunction "18_18") (pintype "passive"))
      (node (ref "J5") (pin "19") (pinfunction "19_19") (pintype "passive"))
      (node (ref "R58") (pin "2") (pinfunction "2_2") (pintype "passive"))
      (node (ref "R686") (pin "2") (pinfunction "2_2") (pintype "passive"))
      (node (ref "R687") (pin "1") (pinfunction "1_1") (pintype "passive"))
      (node (ref "R698") (pin "2") (pinfunction "2_2") (pintype "passive"))
      (node (ref "U113") (pin "5") (pinfunction "VCC_5") (pintype "power_in"))
    )
    (net (code "75") (name "VCC_2V5") (class "Default")
      (node (ref "C297") (pin "1") (pinfunction "1_1") (pintype "passive"))
      (node (ref "C298") (pin "1") (pinfunction "1_1") (pintype "passive"))
      (node (ref "J6") (pin "1") (pinfunction "1_1") (pintype "passive"))
    )
    (net (code "76") (name "VCC_5V0") (class "Default")
      (node (ref "C309") (pin "1") (pinfunction "1_1") (pintype "passive"))
      (node (ref "C313") (pin "1") (pinfunction "1_1") (pintype "passive"))
      (node (ref "C643") (pin "1") (pinfunction "1_1") (pintype "passive"))
      (node (ref "C644") (pin "1") (pinfunction "1_1") (pintype "passive"))
      (node (ref "J38") (pin "1") (pinfunction "1_1") (pintype "passive"))
      (node (ref "J38") (pin "2") (pinfunction "2_2") (pintype "passive"))
      (node (ref "J38") (pin "3") (pinfunction "3_3") (pintype "passive"))
      (node (ref "J6") (pin "10") (pinfunction "10_10") (pintype "passive"))
      (node (ref "J6") (pin "8") (pinfunction "8_8") (pintype "passive"))
    )
    (net (code "77") (name "VCC_12V0") (class "Default")
      (node (ref "C296") (pin "1") (pinfunction "1_1") (pintype "passive"))
      (node (ref "C301") (pin "1") (pinfunction "1_1") (pintype "passive"))
      (node (ref "J6") (pin "7") (pinfunction "7_7") (pintype "passive"))
      (node (ref "J6") (pin "9") (pinfunction "9_9") (pintype "passive"))
    )
    (net (code "78") (name "VDD_1V0") (class "Default")
      (node (ref "C310") (pin "1") (pinfunction "1_1") (pintype "passive"))
      (node (ref "C314") (pin "1") (pinfunction "1_1") (pintype "passive"))
      (node (ref "J6") (pin "2") (pinfunction "2_2") (pintype "passive"))
    )
    (net (code "79") (name "unconnected-(J5-Pad31)") (class "Default")
      (node (ref "J5") (pin "31") (pinfunction "31_31") (pintype "passive+no_connect"))
    )
  )
)
